# power_breakout_board.net
KiCad netlist of a schematic drawn in EAGLE
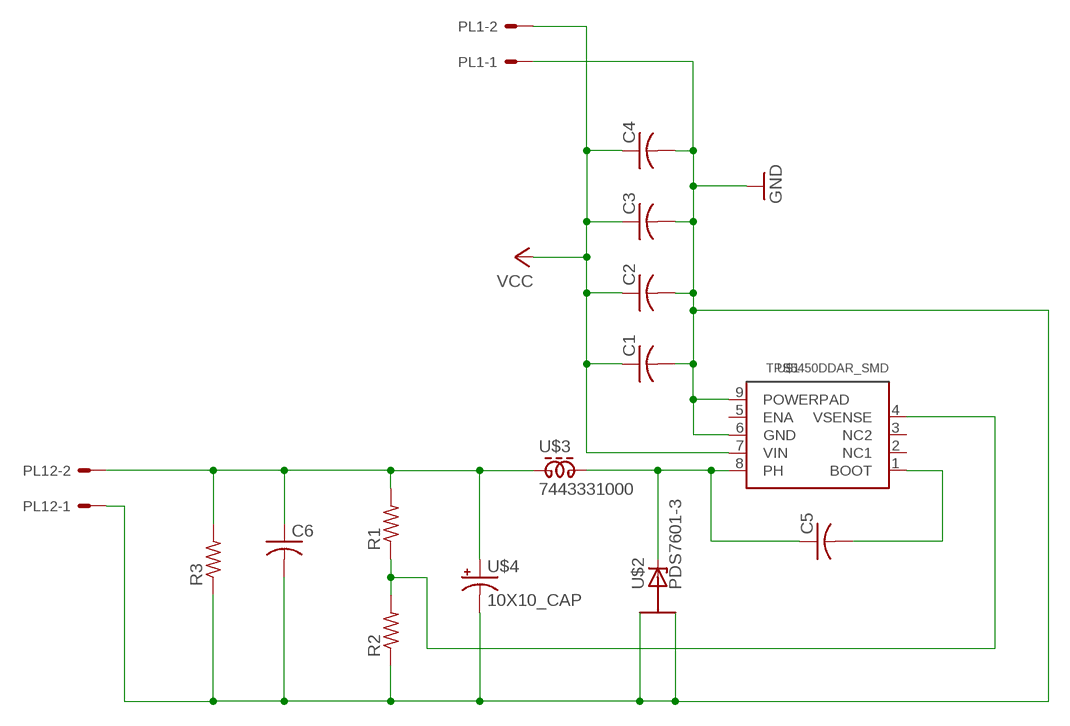
[diagram p0: schematic, sheet 1]

(export (version "E")
  (design (tool "Eeschema 10.0.6"))
  (components
    (comp (ref "C1")
      (value "C-USC1206K")
      (footprint "eagle-import:C1206K")
      (libsource (lib "eagle-import") (part "C-USC1206K"))
    )
    (comp (ref "C2")
      (value "C-USC1206K")
      (footprint "eagle-import:C1206K")
      (libsource (lib "eagle-import") (part "C-USC1206K"))
    )
    (comp (ref "C3")
      (value "C-USC1206K")
      (footprint "eagle-import:C1206K")
      (libsource (lib "eagle-import") (part "C-USC1206K"))
    )
    (comp (ref "C4")
      (value "C-USC1206K")
      (footprint "eagle-import:C1206K")
      (libsource (lib "eagle-import") (part "C-USC1206K"))
    )
    (comp (ref "C5")
      (value "C-USC0805K")
      (footprint "eagle-import:C0805K")
      (libsource (lib "eagle-import") (part "C-USC0805K"))
    )
    (comp (ref "C6")
      (value "C-USC1206K")
      (footprint "eagle-import:C1206K")
      (libsource (lib "eagle-import") (part "C-USC1206K"))
    )
    (comp (ref "PL1")
      (value "555X-2H")
      (footprint "eagle-import:5569-2")
      (libsource (lib "eagle-import") (part "555X-2H"))
    )
    (comp (ref "PL12")
      (value "555X-2H")
      (footprint "eagle-import:5569-2")
      (libsource (lib "eagle-import") (part "555X-2H"))
    )
    (comp (ref "R1")
      (value "R-US_R1206")
      (footprint "eagle-import:R1206")
      (libsource (lib "eagle-import") (part "R-US_R1206"))
    )
    (comp (ref "R2")
      (value "R-US_R1206")
      (footprint "eagle-import:R1206")
      (libsource (lib "eagle-import") (part "R-US_R1206"))
    )
    (comp (ref "R3")
      (value "R-US_R1206")
      (footprint "eagle-import:R1206")
      (libsource (lib "eagle-import") (part "R-US_R1206"))
    )
    (comp (ref "U$1")
      (value "TPS5450DDAR_SMD")
      (footprint "eagle-import:SO-POWERPAD")
      (libsource (lib "eagle-import") (part "TPS5450DDAR_SMD"))
    )
    (comp (ref "U$2")
      (value "PDS7601-3")
      (footprint "eagle-import:POWERDI-5_SMD")
      (libsource (lib "eagle-import") (part "PDS7601-3"))
    )
    (comp (ref "U$3")
      (value "7443331000")
      (footprint "eagle-import:7443331000_SMD")
      (libsource (lib "eagle-import") (part "7443331000"))
    )
    (comp (ref "U$4")
      (value "10X10_CAP")
      (footprint "eagle-import:10X10_CAP_SMD")
      (libsource (lib "eagle-import") (part "10X10_CAP"))
    )
  )
  (nets
    (net (code "1") (name "GND") (class "Default")
      (node (ref "C1") (pin "2") (pinfunction "2_2") (pintype "passive"))
      (node (ref "C2") (pin "2") (pinfunction "2_2") (pintype "passive"))
      (node (ref "C3") (pin "2") (pinfunction "2_2") (pintype "passive"))
      (node (ref "C4") (pin "2") (pinfunction "2_2") (pintype "passive"))
      (node (ref "C6") (pin "2") (pinfunction "2_2") (pintype "passive"))
      (node (ref "PL1") (pin "1") (pinfunction "S_1") (pintype "passive"))
      (node (ref "PL12") (pin "1") (pinfunction "S_1") (pintype "passive"))
      (node (ref "R2") (pin "1") (pinfunction "1_1") (pintype "passive"))
      (node (ref "R3") (pin "1") (pinfunction "1_1") (pintype "passive"))
      (node (ref "U$1") (pin "6") (pinfunction "GND_6") (pintype "bidirectional"))
      (node (ref "U$1") (pin "9") (pinfunction "POWERPAD_9") (pintype "bidirectional"))
      (node (ref "U$2") (pin "LEFT") (pinfunction "LEFT_LEFT") (pintype "bidirectional"))
      (node (ref "U$2") (pin "RIGHT") (pinfunction "RIGHT_RIGHT") (pintype "bidirectional"))
      (node (ref "U$4") (pin "-") (pinfunction "-_-") (pintype "passive"))
    )
    (net (code "2") (name "Net-(PL12B-S)") (class "Default")
      (node (ref "C6") (pin "1") (pinfunction "1_1") (pintype "passive"))
      (node (ref "PL12") (pin "2") (pinfunction "S_2") (pintype "passive"))
      (node (ref "R1") (pin "2") (pinfunction "2_2") (pintype "passive"))
      (node (ref "R3") (pin "2") (pinfunction "2_2") (pintype "passive"))
      (node (ref "U$3") (pin "P1") (pinfunction "1_P1") (pintype "passive"))
      (node (ref "U$4") (pin "+") (pinfunction "+_+") (pintype "passive"))
    )
    (net (code "3") (name "Net-(U$1-BOOT)") (class "Default")
      (node (ref "C5") (pin "2") (pinfunction "2_2") (pintype "passive"))
      (node (ref "U$1") (pin "1") (pinfunction "BOOT_1") (pintype "bidirectional"))
    )
    (net (code "4") (name "Net-(U$1-PH)") (class "Default")
      (node (ref "C5") (pin "1") (pinfunction "1_1") (pintype "passive"))
      (node (ref "U$1") (pin "8") (pinfunction "PH_8") (pintype "bidirectional"))
      (node (ref "U$2") (pin "HEAT") (pinfunction "HEAT_HEAT") (pintype "passive"))
      (node (ref "U$3") (pin "P2") (pinfunction "2_P2") (pintype "passive"))
    )
    (net (code "5") (name "Net-(U$1-VSENSE)") (class "Default")
      (node (ref "R1") (pin "1") (pinfunction "1_1") (pintype "passive"))
      (node (ref "R2") (pin "2") (pinfunction "2_2") (pintype "passive"))
      (node (ref "U$1") (pin "4") (pinfunction "VSENSE_4") (pintype "bidirectional"))
    )
    (net (code "6") (name "VCC") (class "Default")
      (node (ref "C1") (pin "1") (pinfunction "1_1") (pintype "passive"))
      (node (ref "C2") (pin "1") (pinfunction "1_1") (pintype "passive"))
      (node (ref "C3") (pin "1") (pinfunction "1_1") (pintype "passive"))
      (node (ref "C4") (pin "1") (pinfunction "1_1") (pintype "passive"))
      (node (ref "PL1") (pin "2") (pinfunction "S_2") (pintype "passive"))
      (node (ref "U$1") (pin "7") (pinfunction "VIN_7") (pintype "bidirectional"))
    )
    (net (code "7") (name "unconnected-(U$1-ENA-Pad5)") (class "Default")
      (node (ref "U$1") (pin "5") (pinfunction "ENA_5") (pintype "bidirectional"))
    )
    (net (code "8") (name "unconnected-(U$1-NC1-Pad2)") (class "Default")
      (node (ref "U$1") (pin "2") (pinfunction "NC1_2") (pintype "bidirectional"))
    )
    (net (code "9") (name "unconnected-(U$1-NC2-Pad3)") (class "Default")
      (node (ref "U$1") (pin "3") (pinfunction "NC2_3") (pintype "bidirectional"))
    )
  )
)
